# Light_Detector.net
KiCad netlist of a schematic drawn in Altium Designer
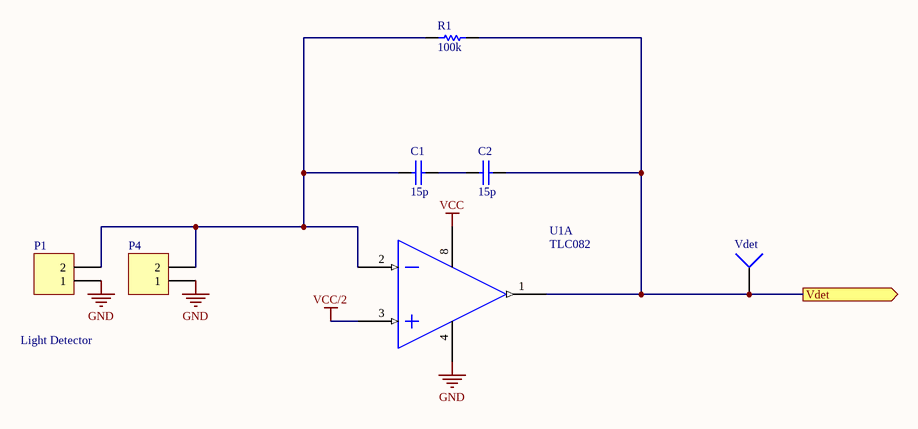
[diagram p0: Light Detector.SchDoc]

(export (version "E")
  (design (tool "Eeschema 10.0.6"))
  (components
    (comp (ref "C1")
      (value "15p")
      (footprint "ece-RAD0.2")
      (description "Capacitor Non Polarised Through Hole")
      (libsource (lib "ece components") (part "CAP"))
    )
    (comp (ref "C2")
      (value "15p")
      (footprint "ece-RAD0.2")
      (description "Capacitor Non Polarised Through Hole")
      (libsource (lib "ece components") (part "CAP"))
    )
    (comp (ref "P1")
      (value "Header 2")
      (footprint "ece-HDR1X2")
      (description "Header, 2-Pin")
      (fields (field (name "PUBLISHER") "Altium Limited"))
      (libsource (lib "ece components") (part "Header 2"))
    )
    (comp (ref "P4")
      (value "Header 2")
      (footprint "ece-HDR1X2")
      (description "Header, 2-Pin")
      (fields (field (name "PUBLISHER") "Altium Limited"))
      (libsource (lib "ece components") (part "Header 2"))
    )
    (comp (ref "R1")
      (value "100k")
      (footprint "ece-AXIAL0.4")
      (description "Resistor")
      (fields (field (name "PUBLISHER") "Altium Limited"))
      (libsource (lib "ece components") (part "Res1"))
    )
    (comp (ref "U1")
      (value "TLC082")
      (footprint "ECE-DIP8")
      (libsource (lib "ece components") (part "TLC082"))
    )
    (comp (ref "VOFF")
      (value "Vdet")
      (footprint "ece-HDR1")
      (description "Socket")
      (fields (field (name "PUBLISHER") "Altium Limited"))
      (libsource (lib "ece components") (part "Test pin"))
    )
  )
  (nets
    (net (code "1") (name "/Vdet") (class "Default")
      (node (ref "C2") (pin "2") (pinfunction "2_2") (pintype "passive"))
      (node (ref "R1") (pin "2") (pinfunction "2_2") (pintype "passive"))
      (node (ref "U1") (pin "1") (pinfunction "OUT1_1") (pintype "output"))
      (node (ref "VOFF") (pin "1") (pinfunction "1_1") (pintype "passive"))
    )
    (net (code "2") (name "GND") (class "Default")
      (node (ref "P1") (pin "1") (pinfunction "1_1") (pintype "passive"))
      (node (ref "P4") (pin "1") (pinfunction "1_1") (pintype "passive"))
      (node (ref "U1") (pin "4") (pinfunction "GND_4") (pintype "power_in"))
    )
    (net (code "3") (name "Net-(C1-Pad2)") (class "Default")
      (node (ref "C1") (pin "2") (pinfunction "2_2") (pintype "passive"))
      (node (ref "C2") (pin "1") (pinfunction "1_1") (pintype "passive"))
    )
    (net (code "4") (name "Net-(U1A-IN1(-))") (class "Default")
      (node (ref "C1") (pin "1") (pinfunction "1_1") (pintype "passive"))
      (node (ref "P1") (pin "2") (pinfunction "2_2") (pintype "passive"))
      (node (ref "P4") (pin "2") (pinfunction "2_2") (pintype "passive"))
      (node (ref "R1") (pin "1") (pinfunction "1_1") (pintype "passive"))
      (node (ref "U1") (pin "2") (pinfunction "IN1(-)_2") (pintype "input"))
    )
    (net (code "5") (name "VCC") (class "Default")
      (node (ref "U1") (pin "8") (pinfunction "V(+)_8") (pintype "power_in"))
    )
    (net (code "6") (name "VCC{slash}2") (class "Default")
      (node (ref "U1") (pin "3") (pinfunction "IN1(+)_3") (pintype "input"))
    )
  )
)
